# MCU.net
KiCad netlist of a schematic drawn in Altium Designer
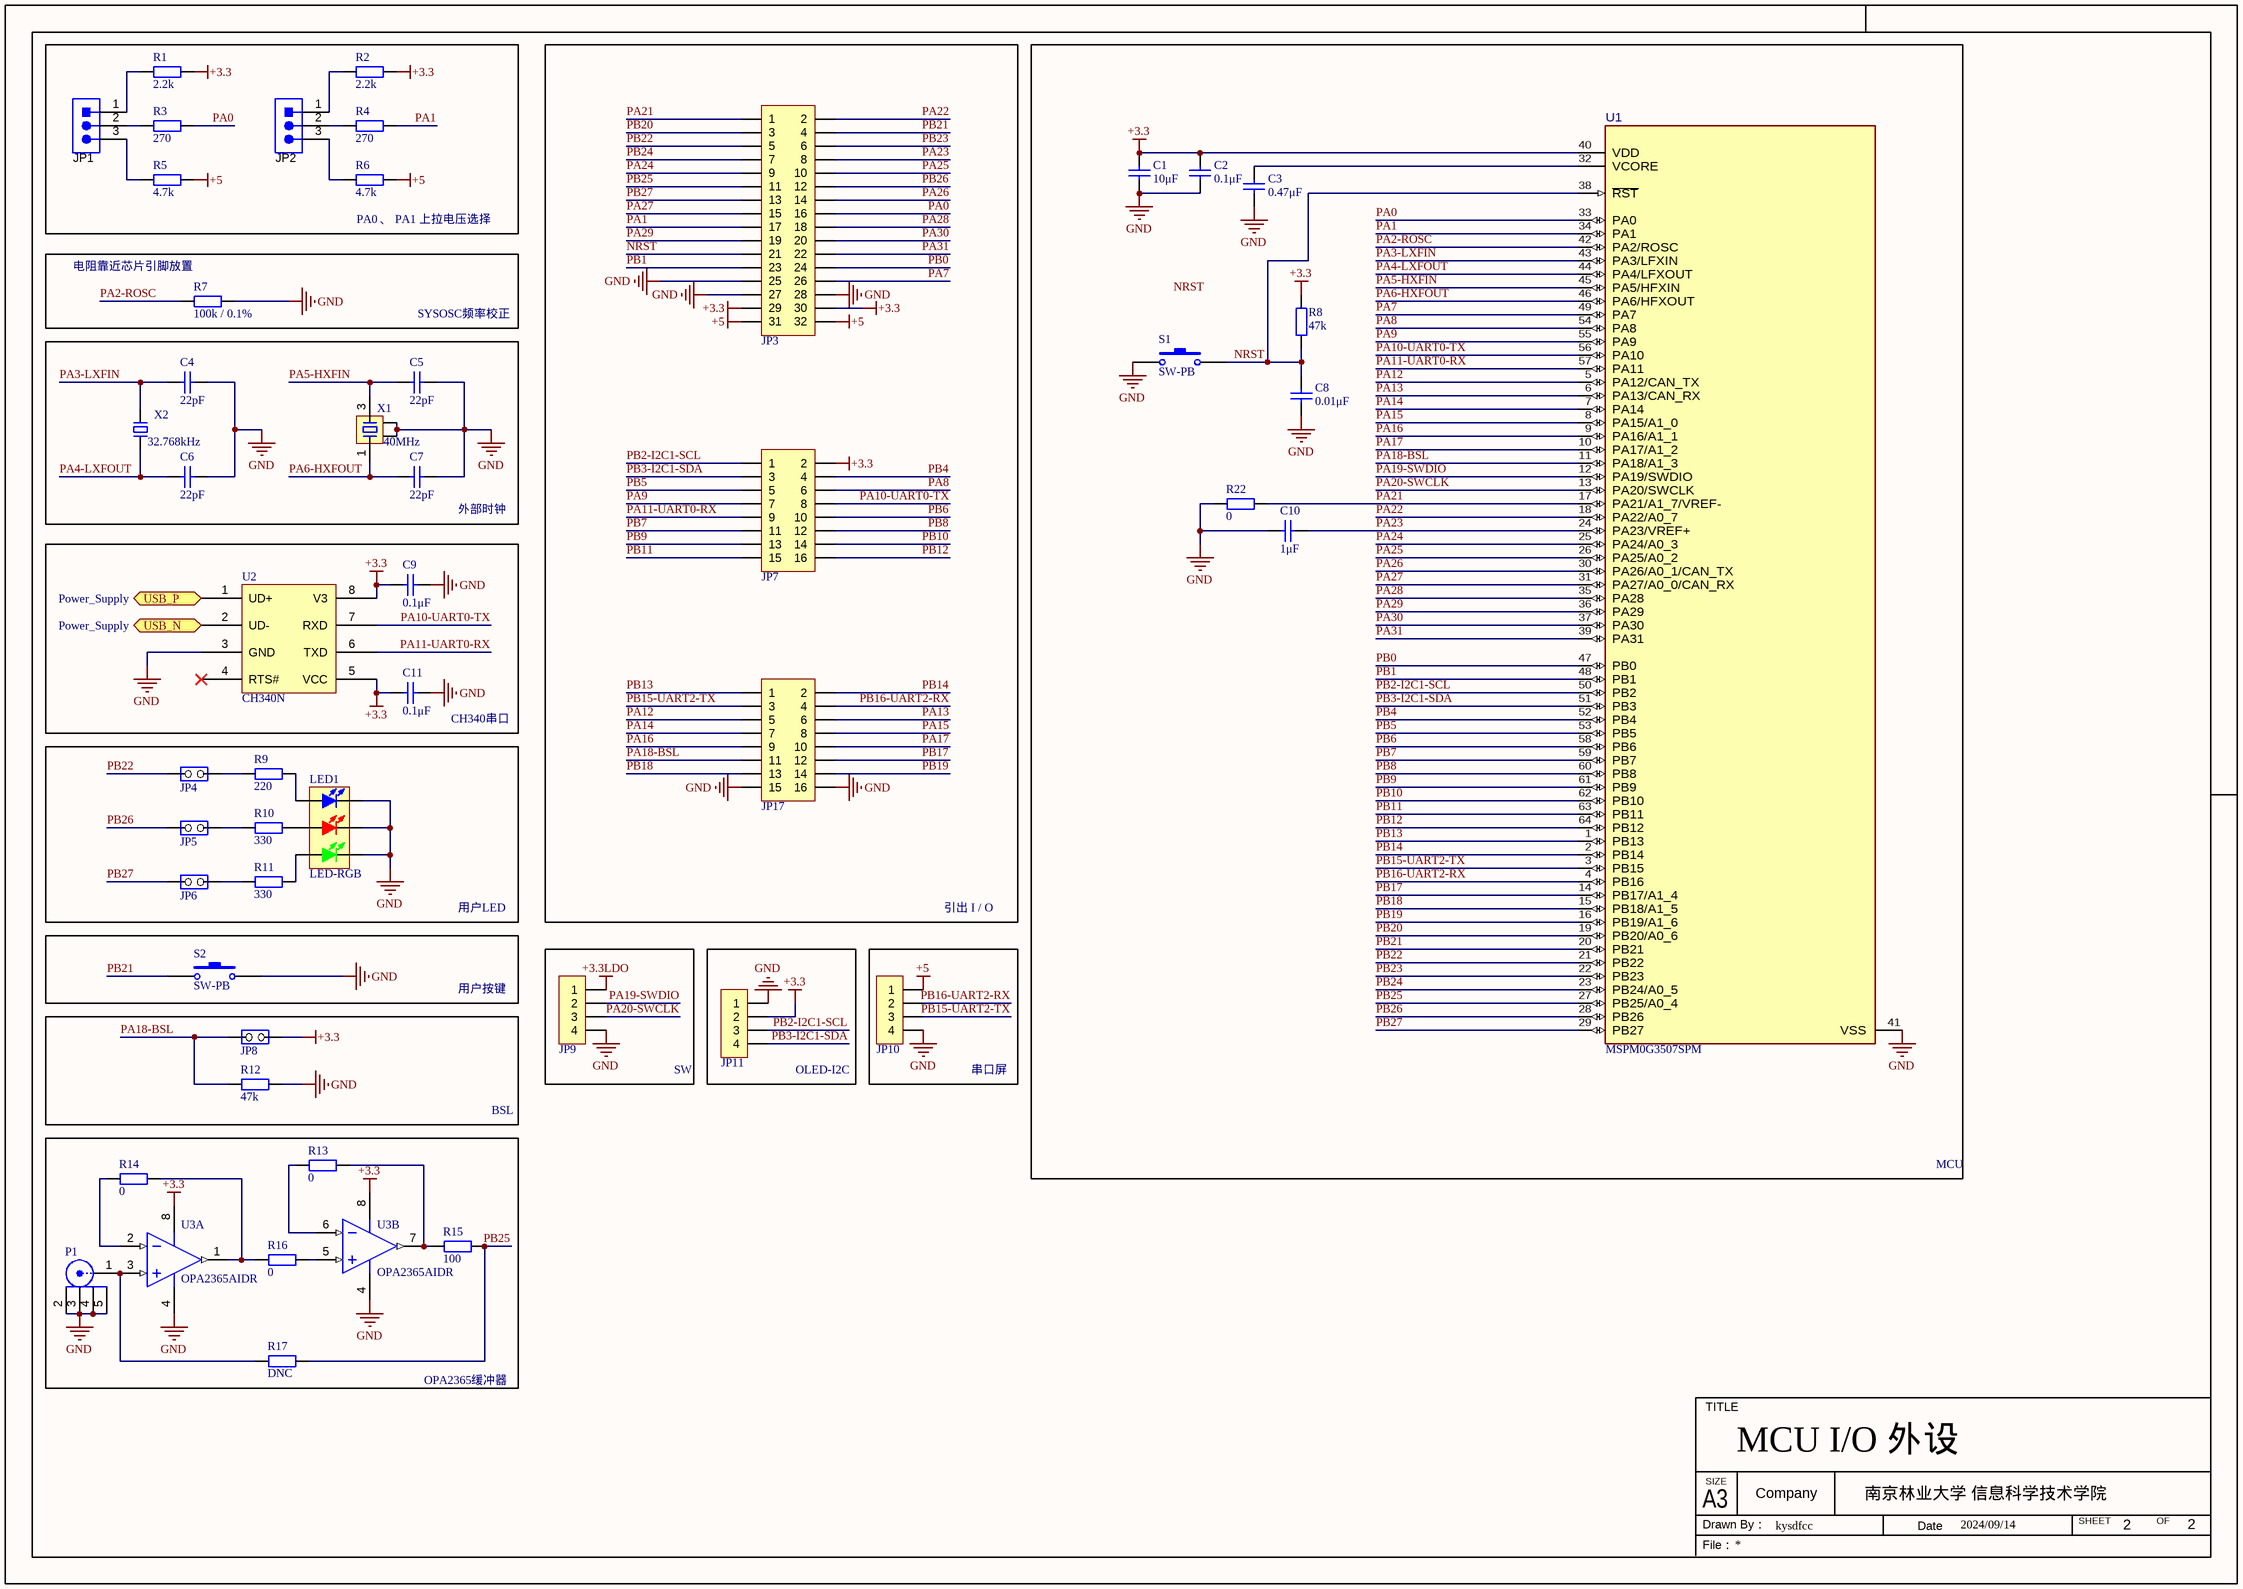
[diagram p0: MCU.SchDoc]

(export (version "E")
  (design (tool "Eeschema 10.0.6"))
  (components
    (comp (ref "C1")
      (value "10μF")
      (footprint "C 0603_L")
      (description "贴片电容")
      (libsource (lib "0.1 - 电阻-电容-电感") (part "C"))
    )
    (comp (ref "C2")
      (value "0.1μF")
      (footprint "C 0603_L")
      (description "贴片电容")
      (libsource (lib "0.1 - 电阻-电容-电感") (part "C"))
    )
    (comp (ref "C3")
      (value "0.47μF")
      (footprint "C 0603_L")
      (description "贴片电容")
      (libsource (lib "0.1 - 电阻-电容-电感") (part "C"))
    )
    (comp (ref "C4")
      (value "22pF")
      (footprint "C 0603_L")
      (description "贴片电容")
      (libsource (lib "0.1 - 电阻-电容-电感") (part "C"))
    )
    (comp (ref "C5")
      (value "22pF")
      (footprint "C 0603_L")
      (description "贴片电容")
      (libsource (lib "0.1 - 电阻-电容-电感") (part "C"))
    )
    (comp (ref "C6")
      (value "22pF")
      (footprint "C 0603_L")
      (description "贴片电容")
      (libsource (lib "0.1 - 电阻-电容-电感") (part "C"))
    )
    (comp (ref "C7")
      (value "22pF")
      (footprint "C 0603_L")
      (description "贴片电容")
      (libsource (lib "0.1 - 电阻-电容-电感") (part "C"))
    )
    (comp (ref "C8")
      (value "0.01μF")
      (footprint "C 0603_L")
      (description "贴片电容")
      (libsource (lib "0.1 - 电阻-电容-电感") (part "C"))
    )
    (comp (ref "C9")
      (value "0.1μF")
      (footprint "C 0603_L")
      (description "贴片电容")
      (libsource (lib "0.1 - 电阻-电容-电感") (part "C"))
    )
    (comp (ref "C10")
      (value "1μF")
      (footprint "C 0603_L")
      (description "贴片电容")
      (libsource (lib "0.1 - 电阻-电容-电感") (part "C"))
    )
    (comp (ref "C11")
      (value "0.1μF")
      (footprint "C 0603_L")
      (description "贴片电容")
      (libsource (lib "0.1 - 电阻-电容-电感") (part "C"))
    )
    (comp (ref "JP1")
      (value "PEC03SAAN")
      (footprint "CONN_PEC03SAAN")
      (description "Header, 100mil, 3x1, Tin, TH")
      (fields
        (field (name "MANUFACTURER") "Sullins Connector Solutions")
        (field (name "PUBLISHER") "Texas Instruments")
      )
      (libsource (lib "Schlib1") (part "Header 3x1"))
    )
    (comp (ref "JP2")
      (value "PEC03SAAN")
      (footprint "CONN_PEC03SAAN")
      (description "Header, 100mil, 3x1, Tin, TH")
      (fields
        (field (name "MANUFACTURER") "Sullins Connector Solutions")
        (field (name "PUBLISHER") "Texas Instruments")
      )
      (libsource (lib "Schlib1") (part "Header 3x1"))
    )
    (comp (ref "JP3")
      (value "Header 2X11")
      (footprint "HDR2.54-LI-2x16P")
      (description "16*2P接插件")
      (libsource (lib "5.4 - 接插件-脚距2.54 (100mil) ") (part "Header 16X2"))
    )
    (comp (ref "JP4")
      (value "Jumper_Header 2x1")
      (footprint "CON_SAMTEC_TSW-102-07-G-S")
      (description "Header, 2x1, 2,54mm, VR, TH, Height 5.84mm/2.54mm")
      (fields (field (name "INTERNAL_PART_NUMBER") "MCD-00045") (field (name "MANUFACTURER") "SAMTEC"))
      (libsource (lib "Schlib1") (part "Header 2x1"))
    )
    (comp (ref "JP5")
      (value "Jumper_Header 2x1")
      (footprint "CON_SAMTEC_TSW-102-07-G-S")
      (description "Header, 2x1, 2,54mm, VR, TH, Height 5.84mm/2.54mm")
      (fields (field (name "INTERNAL_PART_NUMBER") "MCD-00045") (field (name "MANUFACTURER") "SAMTEC"))
      (libsource (lib "Schlib1") (part "Header 2x1"))
    )
    (comp (ref "JP6")
      (value "Jumper_Header 2x1")
      (footprint "CON_SAMTEC_TSW-102-07-G-S")
      (description "Header, 2x1, 2,54mm, VR, TH, Height 5.84mm/2.54mm")
      (fields (field (name "INTERNAL_PART_NUMBER") "MCD-00045") (field (name "MANUFACTURER") "SAMTEC"))
      (libsource (lib "Schlib1") (part "Header 2x1"))
    )
    (comp (ref "JP7")
      (value "Header 8X2")
      (footprint "HDR2.54-LI-2x8P")
      (description "8*2P接插件")
      (libsource (lib "5.4 - 接插件-脚距2.54 (100mil) ") (part "Header 8X2"))
    )
    (comp (ref "JP8")
      (value "Jumper_Header 2x1")
      (footprint "CON_SAMTEC_TSW-102-07-G-S")
      (description "Header, 2x1, 2,54mm, VR, TH, Height 5.84mm/2.54mm")
      (fields (field (name "INTERNAL_PART_NUMBER") "MCD-00045") (field (name "MANUFACTURER") "SAMTEC"))
      (libsource (lib "Schlib1") (part "Header 2x1"))
    )
    (comp (ref "JP9")
      (value "HDR-1X4")
      (footprint "HDR2.54-LI-4P")
      (description "4P接插件")
      (libsource (lib "5.4 - 接插件-脚距2.54 (100mil) ") (part "Header 4"))
    )
    (comp (ref "JP10")
      (value "HDR-1X4")
      (footprint "HDR2.54-LI-4P")
      (description "4P接插件")
      (libsource (lib "5.4 - 接插件-脚距2.54 (100mil) ") (part "Header 4"))
    )
    (comp (ref "JP11")
      (value "HDR-1X4")
      (footprint "HDR2.54-M-LI-4P")
      (description "4P接插件")
      (libsource (lib "5.4 - 接插件-脚距2.54 (100mil) ") (part "Header 4"))
    )
    (comp (ref "JP17")
      (value "Header 8X2")
      (footprint "HDR2.54-LI-2x8P")
      (description "8*2P接插件")
      (libsource (lib "5.4 - 接插件-脚距2.54 (100mil) ") (part "Header 8X2"))
    )
    (comp (ref "LED1")
      (value "LED-RGB")
      (footprint "LED 5050")
      (description "5050三基色LED")
      (libsource (lib "0.3 - LED发光二极管") (part "LED-RGB 5050"))
    )
    (comp (ref "P1")
      (value "~")
      (footprint "TE_5-1814832-1")
      (description "SMA Straight PCB Socket Die Cast, 50 Ohm, TH")
      (fields
        (field (name "MANUFACTURER") "TE Connectivity")
        (field (name "PARTNUMBER") "5-1814832-1")
        (field (name "PUBLISHER") "Texas Instruments")
      )
      (libsource (lib "Schlib1") (part "SMA"))
    )
    (comp (ref "R1")
      (value "2.2k")
      (footprint "R 0603_L")
      (description "贴片电阻")
      (libsource (lib "0.1 - 电阻-电容-电感") (part "R"))
    )
    (comp (ref "R2")
      (value "2.2k")
      (footprint "R 0603_L")
      (description "贴片电阻")
      (libsource (lib "0.1 - 电阻-电容-电感") (part "R"))
    )
    (comp (ref "R3")
      (value "270")
      (footprint "R 0603_L")
      (description "贴片电阻")
      (libsource (lib "0.1 - 电阻-电容-电感") (part "R"))
    )
    (comp (ref "R4")
      (value "270")
      (footprint "R 0603_L")
      (description "贴片电阻")
      (libsource (lib "0.1 - 电阻-电容-电感") (part "R"))
    )
    (comp (ref "R5")
      (value "4.7k")
      (footprint "R 0603_L")
      (description "贴片电阻")
      (libsource (lib "0.1 - 电阻-电容-电感") (part "R"))
    )
    (comp (ref "R6")
      (value "4.7k")
      (footprint "R 0603_L")
      (description "贴片电阻")
      (libsource (lib "0.1 - 电阻-电容-电感") (part "R"))
    )
    (comp (ref "R7")
      (value "100k / 0.1%")
      (footprint "R 0603_L")
      (description "贴片电阻")
      (libsource (lib "0.1 - 电阻-电容-电感") (part "R"))
    )
    (comp (ref "R8")
      (value "47k")
      (footprint "R 0603_L")
      (description "贴片电阻")
      (libsource (lib "0.1 - 电阻-电容-电感") (part "R"))
    )
    (comp (ref "R9")
      (value "220")
      (footprint "R 0603_L")
      (description "贴片电阻")
      (libsource (lib "0.1 - 电阻-电容-电感") (part "R"))
    )
    (comp (ref "R10")
      (value "330")
      (footprint "R 0603_L")
      (description "贴片电阻")
      (libsource (lib "0.1 - 电阻-电容-电感") (part "R"))
    )
    (comp (ref "R11")
      (value "330")
      (footprint "R 0603_L")
      (description "贴片电阻")
      (libsource (lib "0.1 - 电阻-电容-电感") (part "R"))
    )
    (comp (ref "R12")
      (value "47k")
      (footprint "R 0603_L")
      (description "贴片电阻")
      (libsource (lib "0.1 - 电阻-电容-电感") (part "R"))
    )
    (comp (ref "R13")
      (value "0")
      (footprint "R 0603_L")
      (description "贴片电阻")
      (libsource (lib "0.1 - 电阻-电容-电感") (part "R"))
    )
    (comp (ref "R14")
      (value "0")
      (footprint "R 0603_L")
      (description "贴片电阻")
      (libsource (lib "0.1 - 电阻-电容-电感") (part "R"))
    )
    (comp (ref "R15")
      (value "100")
      (footprint "R 0603_L")
      (description "贴片电阻")
      (libsource (lib "0.1 - 电阻-电容-电感") (part "R"))
    )
    (comp (ref "R16")
      (value "0")
      (footprint "R 0603_L")
      (description "贴片电阻")
      (libsource (lib "0.1 - 电阻-电容-电感") (part "R"))
    )
    (comp (ref "R17")
      (value "DNC")
      (footprint "R 0603_L")
      (description "贴片电阻")
      (libsource (lib "0.1 - 电阻-电容-电感") (part "R"))
    )
    (comp (ref "R22")
      (value "0")
      (footprint "R 0603_L")
      (description "贴片电阻")
      (libsource (lib "0.1 - 电阻-电容-电感") (part "R"))
    )
    (comp (ref "S1")
      (value "SW-PB")
      (footprint "SW_PB2_A1")
      (description "微动开关")
      (libsource (lib "0.7 - 常用按键-开关") (part "SW-PB"))
    )
    (comp (ref "S2")
      (value "SW-PB")
      (footprint "SW_PB2_A1")
      (description "微动开关")
      (libsource (lib "0.7 - 常用按键-开关") (part "SW-PB"))
    )
    (comp (ref "U1")
      (value "MSPM0G3507SPM")
      (footprint "PM0064A-MFG")
      (description "Mixed-Signal Microcontrollers With CAN-FD Interface LQFP64")
      (fields (field (name "MANUFACTURER") "Texas Instruments") (field (name "PARTNUMBER") "MSPM0G3507SPM"))
      (libsource (lib "Schlib1") (part "MSPM0G3507"))
    )
    (comp (ref "U2")
      (value "CH340N")
      (footprint "SOP8_N")
      (libsource (lib "1.9 - CH340系列编程器芯片") (part "CH340N"))
    )
    (comp (ref "U3")
      (value "OPA2365AIDR")
      (footprint "D0008A_L")
      (fields (field (name "MANUFACTURER") "Texas Instruments") (field (name "PARTNUMBER") "OPA2365AIDR"))
      (libsource (lib "Schlib1") (part "OPA2365AIDR"))
    )
    (comp (ref "X1")
      (value "40MHz")
      (footprint "OSC 3225-4P")
      (description "4脚无源晶振")
      (libsource (lib "2.0 - 保险丝-晶振-光耦") (part "XTAL-4P"))
    )
    (comp (ref "X2")
      (value "32.768kHz")
      (footprint "OSC 3215-2P")
      (description "2脚无源脚晶振")
      (libsource (lib "2.0 - 保险丝-晶振-光耦") (part "XTAL-2P"))
    )
  )
  (nets
    (net (code "1") (name "+3.3") (class "Default")
      (node (ref "C1") (pin "2") (pinfunction "2_2") (pintype "passive"))
      (node (ref "C11") (pin "2") (pinfunction "2_2") (pintype "passive"))
      (node (ref "C2") (pin "2") (pinfunction "2_2") (pintype "passive"))
      (node (ref "C9") (pin "1") (pinfunction "1_1") (pintype "passive"))
      (node (ref "JP11") (pin "2") (pinfunction "2_2") (pintype "passive"))
      (node (ref "JP3") (pin "29") (pinfunction "29_29") (pintype "passive"))
      (node (ref "JP3") (pin "30") (pinfunction "30_30") (pintype "passive"))
      (node (ref "JP7") (pin "2") (pinfunction "2_2") (pintype "passive"))
      (node (ref "JP8") (pin "2") (pinfunction "NO_2") (pintype "passive"))
      (node (ref "R1") (pin "2") (pinfunction "2_2") (pintype "passive"))
      (node (ref "R2") (pin "2") (pinfunction "2_2") (pintype "passive"))
      (node (ref "R8") (pin "2") (pinfunction "2_2") (pintype "passive"))
      (node (ref "U1") (pin "40") (pinfunction "VDD_40") (pintype "power_in"))
      (node (ref "U2") (pin "5") (pinfunction "VCC_5") (pintype "passive"))
      (node (ref "U2") (pin "8") (pinfunction "V3_8") (pintype "passive"))
      (node (ref "U3") (pin "8") (pinfunction "V+_8") (pintype "power_in"))
    )
    (net (code "2") (name "+3.3LDO") (class "Default")
      (node (ref "JP9") (pin "1") (pinfunction "1_1") (pintype "passive"))
    )
    (net (code "3") (name "+5") (class "Default")
      (node (ref "JP10") (pin "1") (pinfunction "1_1") (pintype "passive"))
      (node (ref "JP3") (pin "31") (pinfunction "31_31") (pintype "passive"))
      (node (ref "JP3") (pin "32") (pinfunction "32_32") (pintype "passive"))
      (node (ref "R5") (pin "1") (pinfunction "1_1") (pintype "passive"))
      (node (ref "R6") (pin "1") (pinfunction "1_1") (pintype "passive"))
    )
    (net (code "4") (name "/NRST") (class "Default")
      (node (ref "C8") (pin "2") (pinfunction "2_2") (pintype "passive"))
      (node (ref "JP3") (pin "21") (pinfunction "21_21") (pintype "passive"))
      (node (ref "R8") (pin "1") (pinfunction "1_1") (pintype "passive"))
      (node (ref "S1") (pin "2") (pinfunction "2_2") (pintype "passive"))
      (node (ref "U1") (pin "38") (pinfunction "~{RST}_38") (pintype "input"))
    )
    (net (code "5") (name "/PA0") (class "Default")
      (node (ref "JP3") (pin "16") (pinfunction "16_16") (pintype "passive"))
      (node (ref "R3") (pin "1") (pinfunction "1_1") (pintype "passive"))
      (node (ref "U1") (pin "33") (pinfunction "PA0_33") (pintype "bidirectional"))
    )
    (net (code "6") (name "/PA1") (class "Default")
      (node (ref "JP3") (pin "17") (pinfunction "17_17") (pintype "passive"))
      (node (ref "R4") (pin "1") (pinfunction "1_1") (pintype "passive"))
      (node (ref "U1") (pin "34") (pinfunction "PA1_34") (pintype "bidirectional"))
    )
    (net (code "7") (name "/PA2-ROSC") (class "Default")
      (node (ref "R7") (pin "2") (pinfunction "2_2") (pintype "passive"))
      (node (ref "U1") (pin "42") (pinfunction "PA2/ROSC_42") (pintype "bidirectional"))
    )
    (net (code "8") (name "/PA3-LXFIN") (class "Default")
      (node (ref "C4") (pin "2") (pinfunction "2_2") (pintype "passive"))
      (node (ref "U1") (pin "43") (pinfunction "PA3/LFXIN_43") (pintype "bidirectional"))
      (node (ref "X2") (pin "2") (pinfunction "2_2") (pintype "passive"))
    )
    (net (code "9") (name "/PA4-LXFOUT") (class "Default")
      (node (ref "C6") (pin "2") (pinfunction "2_2") (pintype "passive"))
      (node (ref "U1") (pin "44") (pinfunction "PA4/LFXOUT_44") (pintype "bidirectional"))
      (node (ref "X2") (pin "1") (pinfunction "1_1") (pintype "passive"))
    )
    (net (code "10") (name "/PA5-HXFIN") (class "Default")
      (node (ref "C5") (pin "2") (pinfunction "2_2") (pintype "passive"))
      (node (ref "U1") (pin "45") (pinfunction "PA5/HFXIN_45") (pintype "bidirectional"))
      (node (ref "X1") (pin "3") (pinfunction "3_3") (pintype "passive"))
    )
    (net (code "11") (name "/PA6-HXFOUT") (class "Default")
      (node (ref "C7") (pin "2") (pinfunction "2_2") (pintype "passive"))
      (node (ref "U1") (pin "46") (pinfunction "PA6/HFXOUT_46") (pintype "bidirectional"))
      (node (ref "X1") (pin "1") (pinfunction "1_1") (pintype "passive"))
    )
    (net (code "12") (name "/PA7") (class "Default")
      (node (ref "JP3") (pin "26") (pinfunction "26_26") (pintype "passive"))
      (node (ref "U1") (pin "49") (pinfunction "PA7_49") (pintype "bidirectional"))
    )
    (net (code "13") (name "/PA8") (class "Default")
      (node (ref "JP7") (pin "6") (pinfunction "6_6") (pintype "passive"))
      (node (ref "U1") (pin "54") (pinfunction "PA8_54") (pintype "bidirectional"))
    )
    (net (code "14") (name "/PA9") (class "Default")
      (node (ref "JP7") (pin "7") (pinfunction "7_7") (pintype "passive"))
      (node (ref "U1") (pin "55") (pinfunction "PA9_55") (pintype "bidirectional"))
    )
    (net (code "15") (name "/PA10-UART0-TX") (class "Default")
      (node (ref "JP7") (pin "8") (pinfunction "8_8") (pintype "passive"))
      (node (ref "U1") (pin "56") (pinfunction "PA10_56") (pintype "bidirectional"))
      (node (ref "U2") (pin "7") (pinfunction "RXD_7") (pintype "passive"))
    )
    (net (code "16") (name "/PA11-UART0-RX") (class "Default")
      (node (ref "JP7") (pin "9") (pinfunction "9_9") (pintype "passive"))
      (node (ref "U1") (pin "57") (pinfunction "PA11_57") (pintype "bidirectional"))
      (node (ref "U2") (pin "6") (pinfunction "TXD_6") (pintype "passive"))
    )
    (net (code "17") (name "/PA12") (class "Default")
      (node (ref "JP17") (pin "5") (pinfunction "5_5") (pintype "passive"))
      (node (ref "U1") (pin "5") (pinfunction "PA12/CAN_TX_5") (pintype "bidirectional"))
    )
    (net (code "18") (name "/PA13") (class "Default")
      (node (ref "JP17") (pin "6") (pinfunction "6_6") (pintype "passive"))
      (node (ref "U1") (pin "6") (pinfunction "PA13/CAN_RX_6") (pintype "bidirectional"))
    )
    (net (code "19") (name "/PA14") (class "Default")
      (node (ref "JP17") (pin "7") (pinfunction "7_7") (pintype "passive"))
      (node (ref "U1") (pin "7") (pinfunction "PA14_7") (pintype "bidirectional"))
    )
    (net (code "20") (name "/PA15") (class "Default")
      (node (ref "JP17") (pin "8") (pinfunction "8_8") (pintype "passive"))
      (node (ref "U1") (pin "8") (pinfunction "PA15/A1_0_8") (pintype "bidirectional"))
    )
    (net (code "21") (name "/PA16") (class "Default")
      (node (ref "JP17") (pin "9") (pinfunction "9_9") (pintype "passive"))
      (node (ref "U1") (pin "9") (pinfunction "PA16/A1_1_9") (pintype "bidirectional"))
    )
    (net (code "22") (name "/PA17") (class "Default")
      (node (ref "JP17") (pin "10") (pinfunction "10_10") (pintype "passive"))
      (node (ref "U1") (pin "10") (pinfunction "PA17/A1_2_10") (pintype "bidirectional"))
    )
    (net (code "23") (name "/PA18-BSL") (class "Default")
      (node (ref "JP17") (pin "11") (pinfunction "11_11") (pintype "passive"))
      (node (ref "JP8") (pin "1") (pinfunction "COMMON_1") (pintype "passive"))
      (node (ref "R12") (pin "2") (pinfunction "2_2") (pintype "passive"))
      (node (ref "U1") (pin "11") (pinfunction "PA18/A1_3_11") (pintype "bidirectional"))
    )
    (net (code "24") (name "/PA19-SWDIO") (class "Default")
      (node (ref "JP9") (pin "2") (pinfunction "2_2") (pintype "passive"))
      (node (ref "U1") (pin "12") (pinfunction "PA19/SWDIO_12") (pintype "bidirectional"))
    )
    (net (code "25") (name "/PA20-SWCLK") (class "Default")
      (node (ref "JP9") (pin "3") (pinfunction "3_3") (pintype "passive"))
      (node (ref "U1") (pin "13") (pinfunction "PA20/SWCLK_13") (pintype "bidirectional"))
    )
    (net (code "26") (name "/PA21") (class "Default")
      (node (ref "JP3") (pin "1") (pinfunction "1_1") (pintype "passive"))
      (node (ref "R22") (pin "1") (pinfunction "1_1") (pintype "passive"))
      (node (ref "U1") (pin "17") (pinfunction "PA21/A1_7/VREF-_17") (pintype "bidirectional"))
    )
    (net (code "27") (name "/PA22") (class "Default")
      (node (ref "JP3") (pin "2") (pinfunction "2_2") (pintype "passive"))
      (node (ref "U1") (pin "18") (pinfunction "PA22/A0_7_18") (pintype "bidirectional"))
    )
    (net (code "28") (name "/PA23") (class "Default")
      (node (ref "C10") (pin "1") (pinfunction "1_1") (pintype "passive"))
      (node (ref "JP3") (pin "8") (pinfunction "8_8") (pintype "passive"))
      (node (ref "U1") (pin "24") (pinfunction "PA23/VREF+_24") (pintype "bidirectional"))
    )
    (net (code "29") (name "/PA24") (class "Default")
      (node (ref "JP3") (pin "9") (pinfunction "9_9") (pintype "passive"))
      (node (ref "U1") (pin "25") (pinfunction "PA24/A0_3_25") (pintype "bidirectional"))
    )
    (net (code "30") (name "/PA25") (class "Default")
      (node (ref "JP3") (pin "10") (pinfunction "10_10") (pintype "passive"))
      (node (ref "U1") (pin "26") (pinfunction "PA25/A0_2_26") (pintype "bidirectional"))
    )
    (net (code "31") (name "/PA26") (class "Default")
      (node (ref "JP3") (pin "14") (pinfunction "14_14") (pintype "passive"))
      (node (ref "U1") (pin "30") (pinfunction "PA26/A0_1/CAN_TX_30") (pintype "bidirectional"))
    )
    (net (code "32") (name "/PA27") (class "Default")
      (node (ref "JP3") (pin "15") (pinfunction "15_15") (pintype "passive"))
      (node (ref "U1") (pin "31") (pinfunction "PA27/A0_0/CAN_RX_31") (pintype "bidirectional"))
    )
    (net (code "33") (name "/PA28") (class "Default")
      (node (ref "JP3") (pin "18") (pinfunction "18_18") (pintype "passive"))
      (node (ref "U1") (pin "35") (pinfunction "PA28_35") (pintype "bidirectional"))
    )
    (net (code "34") (name "/PA29") (class "Default")
      (node (ref "JP3") (pin "19") (pinfunction "19_19") (pintype "passive"))
      (node (ref "U1") (pin "36") (pinfunction "PA29_36") (pintype "bidirectional"))
    )
    (net (code "35") (name "/PA30") (class "Default")
      (node (ref "JP3") (pin "20") (pinfunction "20_20") (pintype "passive"))
      (node (ref "U1") (pin "37") (pinfunction "PA30_37") (pintype "bidirectional"))
    )
    (net (code "36") (name "/PA31") (class "Default")
      (node (ref "JP3") (pin "22") (pinfunction "22_22") (pintype "passive"))
      (node (ref "U1") (pin "39") (pinfunction "PA31_39") (pintype "bidirectional"))
    )
    (net (code "37") (name "/PB0") (class "Default")
      (node (ref "JP3") (pin "24") (pinfunction "24_24") (pintype "passive"))
      (node (ref "U1") (pin "47") (pinfunction "PB0_47") (pintype "bidirectional"))
    )
    (net (code "38") (name "/PB1") (class "Default")
      (node (ref "JP3") (pin "23") (pinfunction "23_23") (pintype "passive"))
      (node (ref "U1") (pin "48") (pinfunction "PB1_48") (pintype "bidirectional"))
    )
    (net (code "39") (name "/PB2-I2C1-SCL") (class "Default")
      (node (ref "JP11") (pin "3") (pinfunction "3_3") (pintype "passive"))
      (node (ref "JP7") (pin "1") (pinfunction "1_1") (pintype "passive"))
      (node (ref "U1") (pin "50") (pinfunction "PB2_50") (pintype "bidirectional"))
    )
    (net (code "40") (name "/PB3-I2C1-SDA") (class "Default")
      (node (ref "JP11") (pin "4") (pinfunction "4_4") (pintype "passive"))
      (node (ref "JP7") (pin "3") (pinfunction "3_3") (pintype "passive"))
      (node (ref "U1") (pin "51") (pinfunction "PB3_51") (pintype "bidirectional"))
    )
    (net (code "41") (name "/PB4") (class "Default")
      (node (ref "JP7") (pin "4") (pinfunction "4_4") (pintype "passive"))
      (node (ref "U1") (pin "52") (pinfunction "PB4_52") (pintype "bidirectional"))
    )
    (net (code "42") (name "/PB5") (class "Default")
      (node (ref "JP7") (pin "5") (pinfunction "5_5") (pintype "passive"))
      (node (ref "U1") (pin "53") (pinfunction "PB5_53") (pintype "bidirectional"))
    )
    (net (code "43") (name "/PB6") (class "Default")
      (node (ref "JP7") (pin "10") (pinfunction "10_10") (pintype "passive"))
      (node (ref "U1") (pin "58") (pinfunction "PB6_58") (pintype "bidirectional"))
    )
    (net (code "44") (name "/PB7") (class "Default")
      (node (ref "JP7") (pin "11") (pinfunction "11_11") (pintype "passive"))
      (node (ref "U1") (pin "59") (pinfunction "PB7_59") (pintype "bidirectional"))
    )
    (net (code "45") (name "/PB8") (class "Default")
      (node (ref "JP7") (pin "12") (pinfunction "12_12") (pintype "passive"))
      (node (ref "U1") (pin "60") (pinfunction "PB8_60") (pintype "bidirectional"))
    )
    (net (code "46") (name "/PB9") (class "Default")
      (node (ref "JP7") (pin "13") (pinfunction "13_13") (pintype "passive"))
      (node (ref "U1") (pin "61") (pinfunction "PB9_61") (pintype "bidirectional"))
    )
    (net (code "47") (name "/PB10") (class "Default")
      (node (ref "JP7") (pin "14") (pinfunction "14_14") (pintype "passive"))
      (node (ref "U1") (pin "62") (pinfunction "PB10_62") (pintype "bidirectional"))
    )
    (net (code "48") (name "/PB11") (class "Default")
      (node (ref "JP7") (pin "15") (pinfunction "15_15") (pintype "passive"))
      (node (ref "U1") (pin "63") (pinfunction "PB11_63") (pintype "bidirectional"))
    )
    (net (code "49") (name "/PB12") (class "Default")
      (node (ref "JP7") (pin "16") (pinfunction "16_16") (pintype "passive"))
      (node (ref "U1") (pin "64") (pinfunction "PB12_64") (pintype "bidirectional"))
    )
    (net (code "50") (name "/PB13") (class "Default")
      (node (ref "JP17") (pin "1") (pinfunction "1_1") (pintype "passive"))
      (node (ref "U1") (pin "1") (pinfunction "PB13_1") (pintype "bidirectional"))
    )
    (net (code "51") (name "/PB14") (class "Default")
      (node (ref "JP17") (pin "2") (pinfunction "2_2") (pintype "passive"))
      (node (ref "U1") (pin "2") (pinfunction "PB14_2") (pintype "bidirectional"))
    )
    (net (code "52") (name "/PB15-UART2-TX") (class "Default")
      (node (ref "JP10") (pin "3") (pinfunction "3_3") (pintype "passive"))
      (node (ref "JP17") (pin "3") (pinfunction "3_3") (pintype "passive"))
      (node (ref "U1") (pin "3") (pinfunction "PB15_3") (pintype "bidirectional"))
    )
    (net (code "53") (name "/PB16-UART2-RX") (class "Default")
      (node (ref "JP10") (pin "2") (pinfunction "2_2") (pintype "passive"))
      (node (ref "JP17") (pin "4") (pinfunction "4_4") (pintype "passive"))
      (node (ref "U1") (pin "4") (pinfunction "PB16_4") (pintype "bidirectional"))
    )
    (net (code "54") (name "/PB17") (class "Default")
      (node (ref "JP17") (pin "12") (pinfunction "12_12") (pintype "passive"))
      (node (ref "U1") (pin "14") (pinfunction "PB17/A1_4_14") (pintype "bidirectional"))
    )
    (net (code "55") (name "/PB18") (class "Default")
      (node (ref "JP17") (pin "13") (pinfunction "13_13") (pintype "passive"))
      (node (ref "U1") (pin "15") (pinfunction "PB18/A1_5_15") (pintype "bidirectional"))
    )
    (net (code "56") (name "/PB19") (class "Default")
      (node (ref "JP17") (pin "14") (pinfunction "14_14") (pintype "passive"))
      (node (ref "U1") (pin "16") (pinfunction "PB19/A1_6_16") (pintype "bidirectional"))
    )
    (net (code "57") (name "/PB20") (class "Default")
      (node (ref "JP3") (pin "3") (pinfunction "3_3") (pintype "passive"))
      (node (ref "U1") (pin "19") (pinfunction "PB20/A0_6_19") (pintype "bidirectional"))
    )
    (net (code "58") (name "/PB21") (class "Default")
      (node (ref "JP3") (pin "4") (pinfunction "4_4") (pintype "passive"))
      (node (ref "S2") (pin "1") (pinfunction "1_1") (pintype "passive"))
      (node (ref "U1") (pin "20") (pinfunction "PB21_20") (pintype "bidirectional"))
    )
    (net (code "59") (name "/PB22") (class "Default")
      (node (ref "JP3") (pin "5") (pinfunction "5_5") (pintype "passive"))
      (node (ref "JP4") (pin "1") (pinfunction "COMMON_1") (pintype "passive"))
      (node (ref "U1") (pin "21") (pinfunction "PB22_21") (pintype "bidirectional"))
    )
    (net (code "60") (name "/PB23") (class "Default")
      (node (ref "JP3") (pin "6") (pinfunction "6_6") (pintype "passive"))
      (node (ref "U1") (pin "22") (pinfunction "PB23_22") (pintype "bidirectional"))
    )
    (net (code "61") (name "/PB24") (class "Default")
      (node (ref "JP3") (pin "7") (pinfunction "7_7") (pintype "passive"))
      (node (ref "U1") (pin "23") (pinfunction "PB24/A0_5_23") (pintype "bidirectional"))
    )
    (net (code "62") (name "/PB25") (class "Default")
      (node (ref "JP3") (pin "11") (pinfunction "11_11") (pintype "passive"))
      (node (ref "R15") (pin "1") (pinfunction "1_1") (pintype "passive"))
      (node (ref "R17") (pin "1") (pinfunction "1_1") (pintype "passive"))
      (node (ref "U1") (pin "27") (pinfunction "PB25/A0_4_27") (pintype "bidirectional"))
    )
    (net (code "63") (name "/PB26") (class "Default")
      (node (ref "JP3") (pin "12") (pinfunction "12_12") (pintype "passive"))
      (node (ref "JP5") (pin "1") (pinfunction "COMMON_1") (pintype "passive"))
      (node (ref "U1") (pin "28") (pinfunction "PB26_28") (pintype "bidirectional"))
    )
    (net (code "64") (name "/PB27") (class "Default")
      (node (ref "JP3") (pin "13") (pinfunction "13_13") (pintype "passive"))
      (node (ref "JP6") (pin "1") (pinfunction "COMMON_1") (pintype "passive"))
      (node (ref "U1") (pin "29") (pinfunction "PB27_29") (pintype "bidirectional"))
    )
    (net (code "65") (name "/USB_N") (class "Default")
      (node (ref "U2") (pin "2") (pinfunction "UD-_2") (pintype "passive"))
    )
    (net (code "66") (name "/USB_P") (class "Default")
      (node (ref "U2") (pin "1") (pinfunction "UD+_1") (pintype "passive"))
    )
    (net (code "67") (name "GND") (class "Default")
      (node (ref "C1") (pin "1") (pinfunction "1_1") (pintype "passive"))
      (node (ref "C10") (pin "2") (pinfunction "2_2") (pintype "passive"))
      (node (ref "C11") (pin "1") (pinfunction "1_1") (pintype "passive"))
      (node (ref "C2") (pin "1") (pinfunction "1_1") (pintype "passive"))
      (node (ref "C3") (pin "1") (pinfunction "1_1") (pintype "passive"))
      (node (ref "C4") (pin "1") (pinfunction "1_1") (pintype "passive"))
      (node (ref "C5") (pin "1") (pinfunction "1_1") (pintype "passive"))
      (node (ref "C6") (pin "1") (pinfunction "1_1") (pintype "passive"))
      (node (ref "C7") (pin "1") (pinfunction "1_1") (pintype "passive"))
      (node (ref "C8") (pin "1") (pinfunction "1_1") (pintype "passive"))
      (node (ref "C9") (pin "2") (pinfunction "2_2") (pintype "passive"))
      (node (ref "JP10") (pin "4") (pinfunction "4_4") (pintype "passive"))
      (node (ref "JP11") (pin "1") (pinfunction "1_1") (pintype "passive"))
      (node (ref "JP17") (pin "15") (pinfunction "15_15") (pintype "passive"))
      (node (ref "JP17") (pin "16") (pinfunction "16_16") (pintype "passive"))
      (node (ref "JP3") (pin "25") (pinfunction "25_25") (pintype "passive"))
      (node (ref "JP3") (pin "27") (pinfunction "27_27") (pintype "passive"))
      (node (ref "JP3") (pin "28") (pinfunction "28_28") (pintype "passive"))
      (node (ref "JP9") (pin "4") (pinfunction "4_4") (pintype "passive"))
      (node (ref "LED1") (pin "1") (pinfunction "BULE_K_1") (pintype "passive"))
      (node (ref "LED1") (pin "3") (pinfunction "RED_K_3") (pintype "passive"))
      (node (ref "LED1") (pin "5") (pinfunction "GREEN_K_5") (pintype "passive"))
      (node (ref "P1") (pin "2") (pinfunction "2_2") (pintype "passive"))
      (node (ref "P1") (pin "3") (pinfunction "3_3") (pintype "passive"))
      (node (ref "P1") (pin "4") (pinfunction "4_4") (pintype "passive"))
      (node (ref "P1") (pin "5") (pinfunction "5_5") (pintype "passive"))
      (node (ref "R12") (pin "1") (pinfunction "1_1") (pintype "passive"))
      (node (ref "R22") (pin "2") (pinfunction "2_2") (pintype "passive"))
      (node (ref "R7") (pin "1") (pinfunction "1_1") (pintype "passive"))
      (node (ref "S1") (pin "1") (pinfunction "1_1") (pintype "passive"))
      (node (ref "S2") (pin "2") (pinfunction "2_2") (pintype "passive"))
      (node (ref "U1") (pin "41") (pinfunction "VSS_41") (pintype "power_in"))
      (node (ref "U2") (pin "3") (pinfunction "GND_3") (pintype "passive"))
      (node (ref "U3") (pin "4") (pinfunction "V-_4") (pintype "power_in"))
      (node (ref "X1") (pin "2") (pinfunction "2_2") (pintype "passive"))
      (node (ref "X1") (pin "4") (pinfunction "4_4") (pintype "passive"))
    )
    (net (code "68") (name "Net-(JP1-Pad1)") (class "Default")
      (node (ref "JP1") (pin "1") (pinfunction "1_1") (pintype "passive"))
      (node (ref "R1") (pin "1") (pinfunction "1_1") (pintype "passive"))
    )
    (net (code "69") (name "Net-(JP1-Pad2)") (class "Default")
      (node (ref "JP1") (pin "2") (pinfunction "2_2") (pintype "passive"))
      (node (ref "R3") (pin "2") (pinfunction "2_2") (pintype "passive"))
    )
    (net (code "70") (name "Net-(JP1-Pad3)") (class "Default")
      (node (ref "JP1") (pin "3") (pinfunction "3_3") (pintype "passive"))
      (node (ref "R5") (pin "2") (pinfunction "2_2") (pintype "passive"))
    )
    (net (code "71") (name "Net-(JP2-Pad1)") (class "Default")
      (node (ref "JP2") (pin "1") (pinfunction "1_1") (pintype "passive"))
      (node (ref "R2") (pin "1") (pinfunction "1_1") (pintype "passive"))
    )
    (net (code "72") (name "Net-(JP2-Pad2)") (class "Default")
      (node (ref "JP2") (pin "2") (pinfunction "2_2") (pintype "passive"))
      (node (ref "R4") (pin "2") (pinfunction "2_2") (pintype "passive"))
    )
    (net (code "73") (name "Net-(JP2-Pad3)") (class "Default")
      (node (ref "JP2") (pin "3") (pinfunction "3_3") (pintype "passive"))
      (node (ref "R6") (pin "2") (pinfunction "2_2") (pintype "passive"))
    )
    (net (code "74") (name "Net-(JP4-NO)") (class "Default")
      (node (ref "JP4") (pin "2") (pinfunction "NO_2") (pintype "passive"))
      (node (ref "R9") (pin "2") (pinfunction "2_2") (pintype "passive"))
    )
    (net (code "75") (name "Net-(JP5-NO)") (class "Default")
      (node (ref "JP5") (pin "2") (pinfunction "NO_2") (pintype "passive"))
      (node (ref "R10") (pin "2") (pinfunction "2_2") (pintype "passive"))
    )
    (net (code "76") (name "Net-(JP6-NO)") (class "Default")
      (node (ref "JP6") (pin "2") (pinfunction "NO_2") (pintype "passive"))
      (node (ref "R11") (pin "2") (pinfunction "2_2") (pintype "passive"))
    )
    (net (code "77") (name "Net-(LED1-BULE_A)") (class "Default")
      (node (ref "LED1") (pin "2") (pinfunction "BULE_A_2") (pintype "passive"))
      (node (ref "R9") (pin "1") (pinfunction "1_1") (pintype "passive"))
    )
    (net (code "78") (name "Net-(LED1-GREEN_A)") (class "Default")
      (node (ref "LED1") (pin "6") (pinfunction "GREEN_A_6") (pintype "passive"))
      (node (ref "R11") (pin "1") (pinfunction "1_1") (pintype "passive"))
    )
    (net (code "79") (name "Net-(LED1-RED_A)") (class "Default")
      (node (ref "LED1") (pin "4") (pinfunction "RED_A_4") (pintype "passive"))
      (node (ref "R10") (pin "1") (pinfunction "1_1") (pintype "passive"))
    )
    (net (code "80") (name "Net-(U1-VCORE)") (class "Default")
      (node (ref "C3") (pin "2") (pinfunction "2_2") (pintype "passive"))
      (node (ref "U1") (pin "32") (pinfunction "VCORE_32") (pintype "power_in"))
    )
    (net (code "81") (name "Net-(U3A-IN_A+)") (class "Default")
      (node (ref "P1") (pin "1") (pinfunction "1_1") (pintype "passive"))
      (node (ref "R17") (pin "2") (pinfunction "2_2") (pintype "passive"))
      (node (ref "U3") (pin "3") (pinfunction "IN_A+_3") (pintype "input"))
    )
    (net (code "82") (name "Net-(U3A-IN_A-)") (class "Default")
      (node (ref "R14") (pin "2") (pinfunction "2_2") (pintype "passive"))
      (node (ref "U3") (pin "2") (pinfunction "IN_A-_2") (pintype "input"))
    )
    (net (code "83") (name "Net-(U3A-VOUT_A)") (class "Default")
      (node (ref "R14") (pin "1") (pinfunction "1_1") (pintype "passive"))
      (node (ref "R16") (pin "2") (pinfunction "2_2") (pintype "passive"))
      (node (ref "U3") (pin "1") (pinfunction "VOUT_A_1") (pintype "output"))
    )
    (net (code "84") (name "Net-(U3B-IN_B+)") (class "Default")
      (node (ref "R16") (pin "1") (pinfunction "1_1") (pintype "passive"))
      (node (ref "U3") (pin "5") (pinfunction "IN_B+_5") (pintype "input"))
    )
    (net (code "85") (name "Net-(U3B-IN_B-)") (class "Default")
      (node (ref "R13") (pin "2") (pinfunction "2_2") (pintype "passive"))
      (node (ref "U3") (pin "6") (pinfunction "IN_B-_6") (pintype "input"))
    )
    (net (code "86") (name "Net-(U3B-VOUT_B)") (class "Default")
      (node (ref "R13") (pin "1") (pinfunction "1_1") (pintype "passive"))
      (node (ref "R15") (pin "2") (pinfunction "2_2") (pintype "passive"))
      (node (ref "U3") (pin "7") (pinfunction "VOUT_B_7") (pintype "output"))
    )
    (net (code "87") (name "unconnected-(U2-RTS#-Pad4)") (class "Default")
      (node (ref "U2") (pin "4") (pinfunction "RTS#_4") (pintype "passive+no_connect"))
    )
  )
)
